# top.net
KiCad netlist of a schematic drawn in Altium Designer
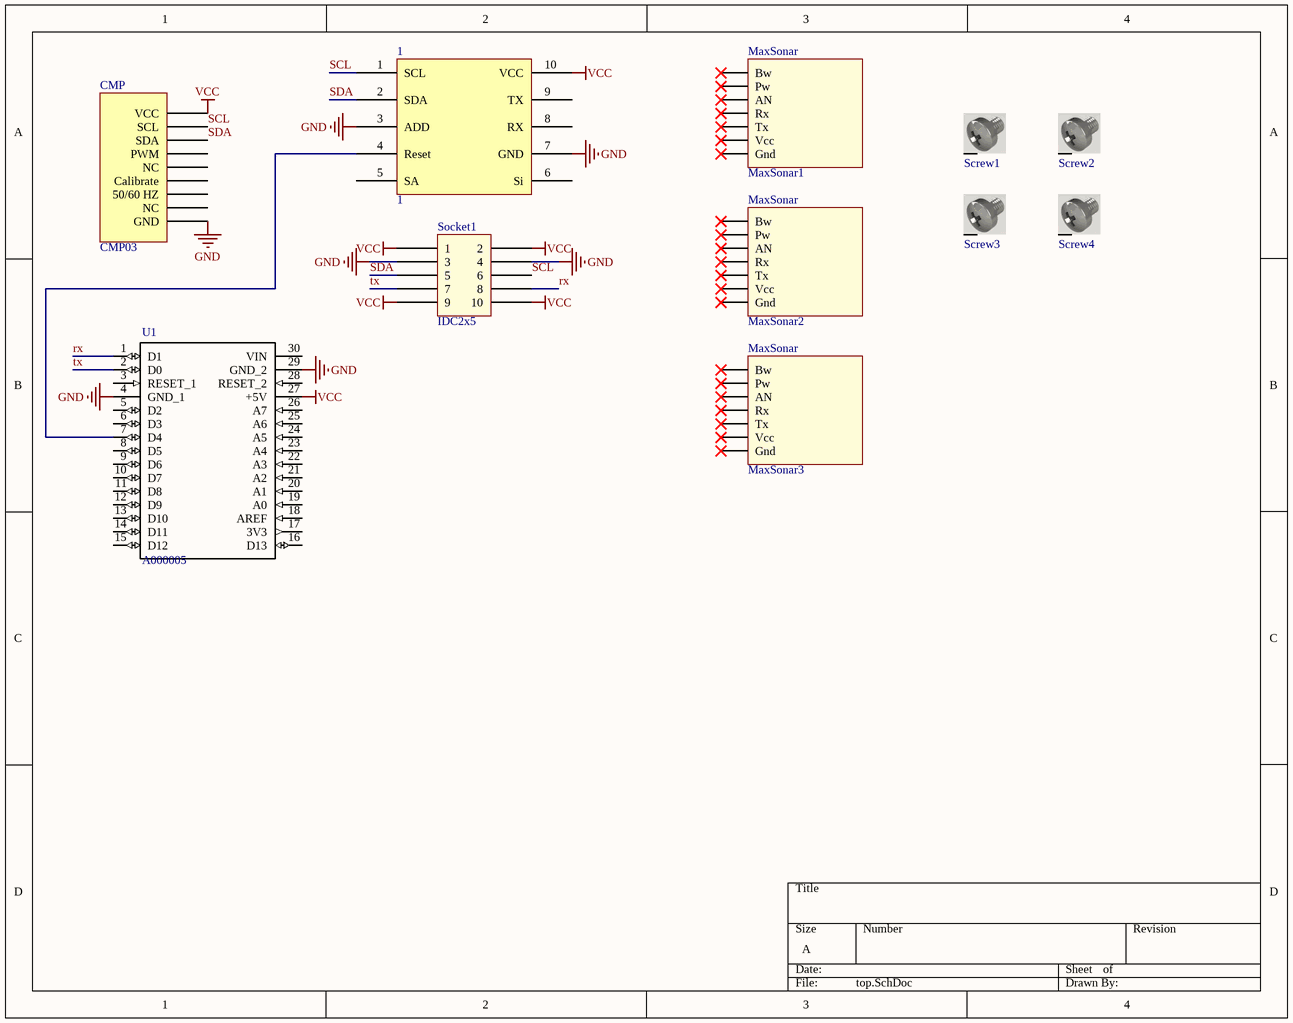
[diagram p0: top.SchDoc]

(export (version "E")
  (design (tool "Eeschema 10.0.6"))
  (components
    (comp (ref "1") (value "1") (footprint "DIP10") (libsource (lib "bno") (part "Component_1")))
    (comp (ref "CMP") (value "CMP03") (footprint "CMP03") (libsource (lib "Farzanegan") (part "CMP03")))
    (comp (ref "MaxSonar1")
      (value "Ultrasonic")
      (footprint "MaxSonar")
      (libsource (lib "Farzanegan") (part "MaxSonar"))
    )
    (comp (ref "MaxSonar2")
      (value "Ultrasonic")
      (footprint "MaxSonar")
      (libsource (lib "Farzanegan") (part "MaxSonar"))
    )
    (comp (ref "MaxSonar3")
      (value "Ultrasonic")
      (footprint "MaxSonar")
      (libsource (lib "Farzanegan") (part "MaxSonar"))
    )
    (comp (ref "Screw1")
      (value "Screw")
      (footprint "Screw")
      (fields (field (name "PUBLISHER") "Altium Limited"))
      (libsource (lib "Farzanegan") (part "Screw"))
    )
    (comp (ref "Screw2")
      (value "Screw")
      (footprint "Screw")
      (fields (field (name "PUBLISHER") "Altium Limited"))
      (libsource (lib "Farzanegan") (part "Screw"))
    )
    (comp (ref "Screw3")
      (value "Screw")
      (footprint "Screw")
      (fields (field (name "PUBLISHER") "Altium Limited"))
      (libsource (lib "Farzanegan") (part "Screw"))
    )
    (comp (ref "Screw4")
      (value "Screw")
      (footprint "Screw")
      (fields (field (name "PUBLISHER") "Altium Limited"))
      (libsource (lib "Farzanegan") (part "Screw"))
    )
    (comp (ref "Socket1")
      (value "IDC2x5")
      (footprint "IDC 2x5")
      (libsource (lib "Farzanegan") (part "IDC 2x5"))
    )
    (comp (ref "U1")
      (value "A000005")
      (footprint "ARDUINO_A000005")
      (description "MICRO, ARDUINO NANO 3.0, MINI-B USB, ATmega328, 0.1DIP, ICSP HDR")
      (fields (field (name "MF") "Arduino"))
      (libsource (lib "Farzanegan") (part "Nano"))
    )
  )
  (nets
    (net (code "1") (name "/SCL") (class "Default")
      (node (ref "1") (pin "1") (pinfunction "SCL_1") (pintype "passive"))
      (node (ref "CMP") (pin "2") (pinfunction "SCL_2") (pintype "passive"))
      (node (ref "Socket1") (pin "6") (pinfunction "6_6") (pintype "passive"))
    )
    (net (code "2") (name "/SDA") (class "Default")
      (node (ref "1") (pin "2") (pinfunction "SDA_2") (pintype "passive"))
      (node (ref "CMP") (pin "3") (pinfunction "SDA_3") (pintype "passive"))
      (node (ref "Socket1") (pin "5") (pinfunction "5_5") (pintype "passive"))
    )
    (net (code "3") (name "/rx") (class "Default")
      (node (ref "Socket1") (pin "8") (pinfunction "8_8") (pintype "passive"))
      (node (ref "U1") (pin "1") (pinfunction "D1_1") (pintype "bidirectional"))
    )
    (net (code "4") (name "/tx") (class "Default")
      (node (ref "Socket1") (pin "7") (pinfunction "7_7") (pintype "passive"))
      (node (ref "U1") (pin "2") (pinfunction "D0_2") (pintype "bidirectional"))
    )
    (net (code "5") (name "GND") (class "Default")
      (node (ref "1") (pin "3") (pinfunction "ADD_3") (pintype "passive"))
      (node (ref "1") (pin "7") (pinfunction "GND_7") (pintype "passive"))
      (node (ref "CMP") (pin "9") (pinfunction "GND_9") (pintype "passive"))
      (node (ref "Socket1") (pin "3") (pinfunction "3_3") (pintype "passive"))
      (node (ref "Socket1") (pin "4") (pinfunction "4_4") (pintype "passive"))
      (node (ref "U1") (pin "29") (pinfunction "GND_2_29") (pintype "power_in"))
      (node (ref "U1") (pin "4") (pinfunction "GND_1_4") (pintype "power_in"))
    )
    (net (code "6") (name "Net-(1-Reset)") (class "Default")
      (node (ref "1") (pin "4") (pinfunction "Reset_4") (pintype "passive"))
      (node (ref "U1") (pin "7") (pinfunction "D4_7") (pintype "bidirectional"))
    )
    (net (code "7") (name "VCC") (class "Default")
      (node (ref "1") (pin "10") (pinfunction "VCC_10") (pintype "passive"))
      (node (ref "CMP") (pin "1") (pinfunction "VCC_1") (pintype "passive"))
      (node (ref "Socket1") (pin "1") (pinfunction "1_1") (pintype "passive"))
      (node (ref "Socket1") (pin "10") (pinfunction "10_10") (pintype "passive"))
      (node (ref "Socket1") (pin "2") (pinfunction "2_2") (pintype "passive"))
      (node (ref "Socket1") (pin "9") (pinfunction "9_9") (pintype "passive"))
      (node (ref "U1") (pin "27") (pinfunction "+5V_27") (pintype "power_in"))
    )
    (net (code "8") (name "unconnected-(1-RX-Pad8)") (class "Default")
      (node (ref "1") (pin "8") (pinfunction "RX_8") (pintype "passive"))
    )
    (net (code "9") (name "unconnected-(1-SA-Pad5)") (class "Default")
      (node (ref "1") (pin "5") (pinfunction "SA_5") (pintype "passive"))
    )
    (net (code "10") (name "unconnected-(1-Si-Pad6)") (class "Default")
      (node (ref "1") (pin "6") (pinfunction "Si_6") (pintype "passive"))
    )
    (net (code "11") (name "unconnected-(1-TX-Pad9)") (class "Default")
      (node (ref "1") (pin "9") (pinfunction "TX_9") (pintype "passive"))
    )
    (net (code "12") (name "unconnected-(CMP-50{slash}60_HZ-Pad7)") (class "Default")
      (node (ref "CMP") (pin "7") (pinfunction "50/60_HZ_7") (pintype "passive"))
    )
    (net (code "13") (name "unconnected-(CMP-Calibrate-Pad6)") (class "Default")
      (node (ref "CMP") (pin "6") (pinfunction "Calibrate_6") (pintype "passive"))
    )
    (net (code "14") (name "unconnected-(CMP-NC-Pad5)") (class "Default")
      (node (ref "CMP") (pin "5") (pinfunction "NC_5") (pintype "passive"))
    )
    (net (code "15") (name "unconnected-(CMP-NC-Pad8)") (class "Default")
      (node (ref "CMP") (pin "8") (pinfunction "NC_8") (pintype "passive"))
    )
    (net (code "16") (name "unconnected-(CMP-PWM-Pad4)") (class "Default")
      (node (ref "CMP") (pin "4") (pinfunction "PWM_4") (pintype "passive"))
    )
    (net (code "17") (name "unconnected-(MaxSonar1-AN-Pad3)") (class "Default")
      (node (ref "MaxSonar1") (pin "3") (pinfunction "AN_3") (pintype "passive+no_connect"))
    )
    (net (code "18") (name "unconnected-(MaxSonar1-Bw-Pad1)") (class "Default")
      (node (ref "MaxSonar1") (pin "1") (pinfunction "Bw_1") (pintype "passive+no_connect"))
    )
    (net (code "19") (name "unconnected-(MaxSonar1-Gnd-Pad7)") (class "Default")
      (node (ref "MaxSonar1") (pin "7") (pinfunction "Gnd_7") (pintype "passive+no_connect"))
    )
    (net (code "20") (name "unconnected-(MaxSonar1-Pw-Pad2)") (class "Default")
      (node (ref "MaxSonar1") (pin "2") (pinfunction "Pw_2") (pintype "passive+no_connect"))
    )
    (net (code "21") (name "unconnected-(MaxSonar1-Rx-Pad4)") (class "Default")
      (node (ref "MaxSonar1") (pin "4") (pinfunction "Rx_4") (pintype "passive+no_connect"))
    )
    (net (code "22") (name "unconnected-(MaxSonar1-Tx-Pad5)") (class "Default")
      (node (ref "MaxSonar1") (pin "5") (pinfunction "Tx_5") (pintype "passive+no_connect"))
    )
    (net (code "23") (name "unconnected-(MaxSonar1-Vcc-Pad6)") (class "Default")
      (node (ref "MaxSonar1") (pin "6") (pinfunction "Vcc_6") (pintype "passive+no_connect"))
    )
    (net (code "24") (name "unconnected-(MaxSonar2-AN-Pad3)") (class "Default")
      (node (ref "MaxSonar2") (pin "3") (pinfunction "AN_3") (pintype "passive+no_connect"))
    )
    (net (code "25") (name "unconnected-(MaxSonar2-Bw-Pad1)") (class "Default")
      (node (ref "MaxSonar2") (pin "1") (pinfunction "Bw_1") (pintype "passive+no_connect"))
    )
    (net (code "26") (name "unconnected-(MaxSonar2-Gnd-Pad7)") (class "Default")
      (node (ref "MaxSonar2") (pin "7") (pinfunction "Gnd_7") (pintype "passive+no_connect"))
    )
    (net (code "27") (name "unconnected-(MaxSonar2-Pw-Pad2)") (class "Default")
      (node (ref "MaxSonar2") (pin "2") (pinfunction "Pw_2") (pintype "passive+no_connect"))
    )
    (net (code "28") (name "unconnected-(MaxSonar2-Rx-Pad4)") (class "Default")
      (node (ref "MaxSonar2") (pin "4") (pinfunction "Rx_4") (pintype "passive+no_connect"))
    )
    (net (code "29") (name "unconnected-(MaxSonar2-Tx-Pad5)") (class "Default")
      (node (ref "MaxSonar2") (pin "5") (pinfunction "Tx_5") (pintype "passive+no_connect"))
    )
    (net (code "30") (name "unconnected-(MaxSonar2-Vcc-Pad6)") (class "Default")
      (node (ref "MaxSonar2") (pin "6") (pinfunction "Vcc_6") (pintype "passive+no_connect"))
    )
    (net (code "31") (name "unconnected-(MaxSonar3-AN-Pad3)") (class "Default")
      (node (ref "MaxSonar3") (pin "3") (pinfunction "AN_3") (pintype "passive+no_connect"))
    )
    (net (code "32") (name "unconnected-(MaxSonar3-Bw-Pad1)") (class "Default")
      (node (ref "MaxSonar3") (pin "1") (pinfunction "Bw_1") (pintype "passive+no_connect"))
    )
    (net (code "33") (name "unconnected-(MaxSonar3-Gnd-Pad7)") (class "Default")
      (node (ref "MaxSonar3") (pin "7") (pinfunction "Gnd_7") (pintype "passive+no_connect"))
    )
    (net (code "34") (name "unconnected-(MaxSonar3-Pw-Pad2)") (class "Default")
      (node (ref "MaxSonar3") (pin "2") (pinfunction "Pw_2") (pintype "passive+no_connect"))
    )
    (net (code "35") (name "unconnected-(MaxSonar3-Rx-Pad4)") (class "Default")
      (node (ref "MaxSonar3") (pin "4") (pinfunction "Rx_4") (pintype "passive+no_connect"))
    )
    (net (code "36") (name "unconnected-(MaxSonar3-Tx-Pad5)") (class "Default")
      (node (ref "MaxSonar3") (pin "5") (pinfunction "Tx_5") (pintype "passive+no_connect"))
    )
    (net (code "37") (name "unconnected-(MaxSonar3-Vcc-Pad6)") (class "Default")
      (node (ref "MaxSonar3") (pin "6") (pinfunction "Vcc_6") (pintype "passive+no_connect"))
    )
    (net (code "38") (name "unconnected-(Screw1-PadS)") (class "Default")
      (node (ref "Screw1") (pin "S") (pinfunction "S_S") (pintype "passive"))
    )
    (net (code "39") (name "unconnected-(Screw2-PadS)") (class "Default")
      (node (ref "Screw2") (pin "S") (pinfunction "S_S") (pintype "passive"))
    )
    (net (code "40") (name "unconnected-(Screw3-PadS)") (class "Default")
      (node (ref "Screw3") (pin "S") (pinfunction "S_S") (pintype "passive"))
    )
    (net (code "41") (name "unconnected-(Screw4-PadS)") (class "Default")
      (node (ref "Screw4") (pin "S") (pinfunction "S_S") (pintype "passive"))
    )
    (net (code "42") (name "unconnected-(U1-3V3-Pad17)") (class "Default")
      (node (ref "U1") (pin "17") (pinfunction "3V3_17") (pintype "output"))
    )
    (net (code "43") (name "unconnected-(U1-A0-Pad19)") (class "Default")
      (node (ref "U1") (pin "19") (pinfunction "A0_19") (pintype "input"))
    )
    (net (code "44") (name "unconnected-(U1-A1-Pad20)") (class "Default")
      (node (ref "U1") (pin "20") (pinfunction "A1_20") (pintype "input"))
    )
    (net (code "45") (name "unconnected-(U1-A2-Pad21)") (class "Default")
      (node (ref "U1") (pin "21") (pinfunction "A2_21") (pintype "input"))
    )
    (net (code "46") (name "unconnected-(U1-A3-Pad22)") (class "Default")
      (node (ref "U1") (pin "22") (pinfunction "A3_22") (pintype "input"))
    )
    (net (code "47") (name "unconnected-(U1-A4-Pad23)") (class "Default")
      (node (ref "U1") (pin "23") (pinfunction "A4_23") (pintype "input"))
    )
    (net (code "48") (name "unconnected-(U1-A5-Pad24)") (class "Default")
      (node (ref "U1") (pin "24") (pinfunction "A5_24") (pintype "input"))
    )
    (net (code "49") (name "unconnected-(U1-A6-Pad25)") (class "Default")
      (node (ref "U1") (pin "25") (pinfunction "A6_25") (pintype "input"))
    )
    (net (code "50") (name "unconnected-(U1-A7-Pad26)") (class "Default")
      (node (ref "U1") (pin "26") (pinfunction "A7_26") (pintype "input"))
    )
    (net (code "51") (name "unconnected-(U1-AREF-Pad18)") (class "Default")
      (node (ref "U1") (pin "18") (pinfunction "AREF_18") (pintype "input"))
    )
    (net (code "52") (name "unconnected-(U1-D2-Pad5)") (class "Default")
      (node (ref "U1") (pin "5") (pinfunction "D2_5") (pintype "bidirectional"))
    )
    (net (code "53") (name "unconnected-(U1-D3-Pad6)") (class "Default")
      (node (ref "U1") (pin "6") (pinfunction "D3_6") (pintype "bidirectional"))
    )
    (net (code "54") (name "unconnected-(U1-D5-Pad8)") (class "Default")
      (node (ref "U1") (pin "8") (pinfunction "D5_8") (pintype "bidirectional"))
    )
    (net (code "55") (name "unconnected-(U1-D6-Pad9)") (class "Default")
      (node (ref "U1") (pin "9") (pinfunction "D6_9") (pintype "bidirectional"))
    )
    (net (code "56") (name "unconnected-(U1-D7-Pad10)") (class "Default")
      (node (ref "U1") (pin "10") (pinfunction "D7_10") (pintype "bidirectional"))
    )
    (net (code "57") (name "unconnected-(U1-D8-Pad11)") (class "Default")
      (node (ref "U1") (pin "11") (pinfunction "D8_11") (pintype "bidirectional"))
    )
    (net (code "58") (name "unconnected-(U1-D9-Pad12)") (class "Default")
      (node (ref "U1") (pin "12") (pinfunction "D9_12") (pintype "bidirectional"))
    )
    (net (code "59") (name "unconnected-(U1-D10-Pad13)") (class "Default")
      (node (ref "U1") (pin "13") (pinfunction "D10_13") (pintype "bidirectional"))
    )
    (net (code "60") (name "unconnected-(U1-D11-Pad14)") (class "Default")
      (node (ref "U1") (pin "14") (pinfunction "D11_14") (pintype "bidirectional"))
    )
    (net (code "61") (name "unconnected-(U1-D12-Pad15)") (class "Default")
      (node (ref "U1") (pin "15") (pinfunction "D12_15") (pintype "bidirectional"))
    )
    (net (code "62") (name "unconnected-(U1-D13-Pad16)") (class "Default")
      (node (ref "U1") (pin "16") (pinfunction "D13_16") (pintype "bidirectional"))
    )
    (net (code "63") (name "unconnected-(U1-RESET_1-Pad3)") (class "Default")
      (node (ref "U1") (pin "3") (pinfunction "RESET_1_3") (pintype "input"))
    )
    (net (code "64") (name "unconnected-(U1-RESET_2-Pad28)") (class "Default")
      (node (ref "U1") (pin "28") (pinfunction "RESET_2_28") (pintype "input"))
    )
    (net (code "65") (name "unconnected-(U1-VIN-Pad30)") (class "Default")
      (node (ref "U1") (pin "30") (pinfunction "VIN_30") (pintype "power_in"))
    )
  )
)
